# Starboard_Deployable_Headers.net
KiCad netlist of a schematic drawn in Altium Designer
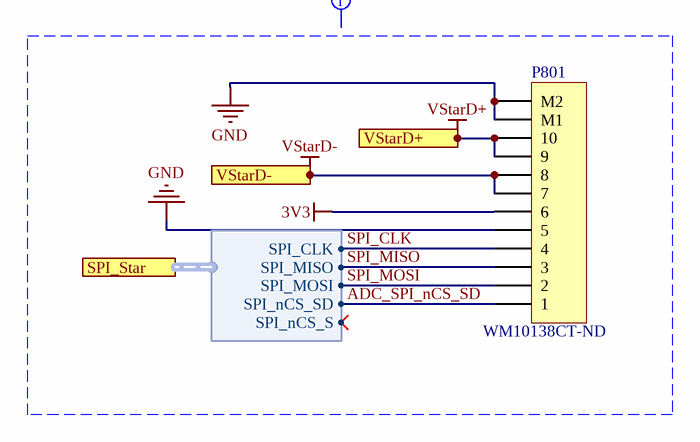
[diagram p0: Starboard_Deployable_Headers.SchDoc]

(export (version "E")
  (design (tool "Eeschema 10.0.6"))
  (components
    (comp (ref "P801")
      (value "WM10138CT-ND")
      (footprint "MOLX-5040501091")
      (description "CONN HEADER SMD R/A 10POS 1.5MM")
      (fields
        (field (name "PART NUMBER") "69")
        (field (name "MANUFACTURER PART NUMBER") "5040501091")
        (field (name "PUBLISHER") "Altium Limited")
      )
      (libsource (lib "Database") (part "Header 12"))
    )
  )
  (nets
    (net (code "2") (name "/ADC_SPI_nCS_SD") (class "Default")
      (node (ref "P801") (pin "1") (pinfunction "1_1") (pintype "passive"))
    )
    (net (code "3") (name "/SPI_CLK") (class "Default")
      (node (ref "P801") (pin "4") (pinfunction "4_4") (pintype "passive"))
    )
    (net (code "4") (name "/SPI_MISO") (class "Default")
      (node (ref "P801") (pin "3") (pinfunction "3_3") (pintype "passive"))
    )
    (net (code "5") (name "/SPI_MOSI") (class "Default")
      (node (ref "P801") (pin "2") (pinfunction "2_2") (pintype "passive"))
    )
    (net (code "7") (name "3V3") (class "Default")
      (node (ref "P801") (pin "6") (pinfunction "6_6") (pintype "passive"))
    )
    (net (code "8") (name "GND") (class "Default")
      (node (ref "P801") (pin "5") (pinfunction "5_5") (pintype "passive"))
      (node (ref "P801") (pin "M1") (pinfunction "M1_M1") (pintype "passive"))
      (node (ref "P801") (pin "M2") (pinfunction "M2_M2") (pintype "passive"))
    )
    (net (code "9") (name "VStarD+") (class "Default")
      (node (ref "P801") (pin "10") (pinfunction "10_10") (pintype "passive"))
      (node (ref "P801") (pin "9") (pinfunction "9_9") (pintype "passive"))
    )
    (net (code "10") (name "VStarD-") (class "Default")
      (node (ref "P801") (pin "7") (pinfunction "7_7") (pintype "passive"))
      (node (ref "P801") (pin "8") (pinfunction "8_8") (pintype "passive"))
    )
  )
)
